# CardSlot.net
KiCad netlist of a schematic drawn in Altium Designer
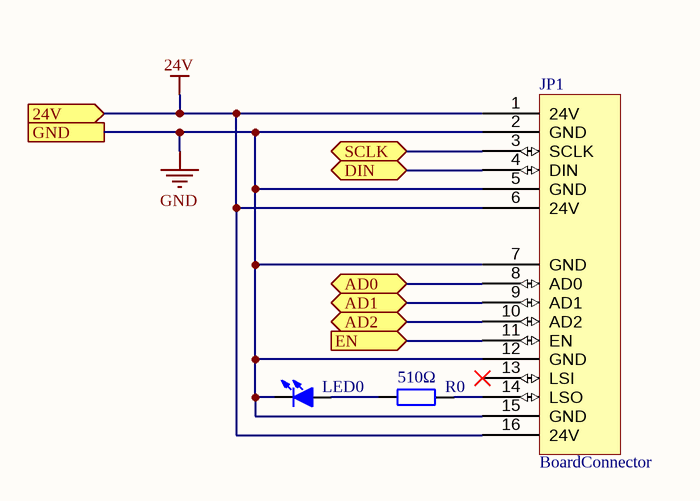
[diagram p0: CardSlot.SchDoc]

(export (version "E")
  (design (tool "Eeschema 10.0.6"))
  (components
    (comp (ref "JP1")
      (value "BoardConnector")
      (footprint "HDR2.54-DIY16-N")
      (description "DIY Board Connector (P/N)")
      (libsource (lib "CustomizedComponents") (part "BoardConnector"))
    )
    (comp (ref "LED0")
      (value "White")
      (footprint "LED 0603W")
      (description "贴片LED")
      (fields (field (name "版权归属") "封装库来自淘宝 ID：黄晶宝石"))
      (libsource (lib "0.3 - LED发光二极管") (part "LED-SMD"))
    )
    (comp (ref "R0")
      (value "510Ω")
      (footprint "R 0603_L")
      (description "贴片电阻")
      (fields (field (name "版权归属") "来自淘宝 ID：黄晶宝石"))
      (libsource (lib "0.1 - 电阻-电容-电感") (part "R"))
    )
  )
  (nets
    (net (code "1") (name "/AD0") (class "Default")
      (node (ref "JP1") (pin "8") (pinfunction "AD0_8") (pintype "bidirectional"))
    )
    (net (code "2") (name "/AD1") (class "Default")
      (node (ref "JP1") (pin "9") (pinfunction "AD1_9") (pintype "bidirectional"))
    )
    (net (code "3") (name "/AD2") (class "Default")
      (node (ref "JP1") (pin "10") (pinfunction "AD2_10") (pintype "bidirectional"))
    )
    (net (code "4") (name "/DIN") (class "Default")
      (node (ref "JP1") (pin "4") (pinfunction "DIN_4") (pintype "bidirectional"))
    )
    (net (code "5") (name "/EN") (class "Default")
      (node (ref "JP1") (pin "11") (pinfunction "EN_11") (pintype "bidirectional"))
    )
    (net (code "6") (name "/SCLK") (class "Default")
      (node (ref "JP1") (pin "3") (pinfunction "SCLK_3") (pintype "bidirectional"))
    )
    (net (code "7") (name "24V") (class "Default")
      (node (ref "JP1") (pin "1") (pinfunction "24V_1") (pintype "passive"))
      (node (ref "JP1") (pin "16") (pinfunction "24V_16") (pintype "passive"))
      (node (ref "JP1") (pin "6") (pinfunction "24V_6") (pintype "passive"))
    )
    (net (code "8") (name "GND") (class "Default")
      (node (ref "JP1") (pin "12") (pinfunction "GND_12") (pintype "passive"))
      (node (ref "JP1") (pin "15") (pinfunction "GND_15") (pintype "passive"))
      (node (ref "JP1") (pin "2") (pinfunction "GND_2") (pintype "passive"))
      (node (ref "JP1") (pin "5") (pinfunction "GND_5") (pintype "passive"))
      (node (ref "JP1") (pin "7") (pinfunction "GND_7") (pintype "passive"))
      (node (ref "LED0") (pin "2") (pinfunction "K_2") (pintype "passive"))
    )
    (net (code "9") (name "Net-(JP1-LSO)") (class "Default")
      (node (ref "JP1") (pin "14") (pinfunction "LSO_14") (pintype "bidirectional"))
      (node (ref "R0") (pin "2") (pinfunction "2_2") (pintype "passive"))
    )
    (net (code "10") (name "Net-(LED0-A)") (class "Default")
      (node (ref "LED0") (pin "1") (pinfunction "A_1") (pintype "passive"))
      (node (ref "R0") (pin "1") (pinfunction "1_1") (pintype "passive"))
    )
    (net (code "11") (name "unconnected-(JP1-LSI-Pad13)") (class "Default")
      (node (ref "JP1") (pin "13") (pinfunction "LSI_13") (pintype "bidirectional+no_connect"))
    )
  )
)
